# contra1575.net
KiCad netlist of a schematic drawn in EAGLE
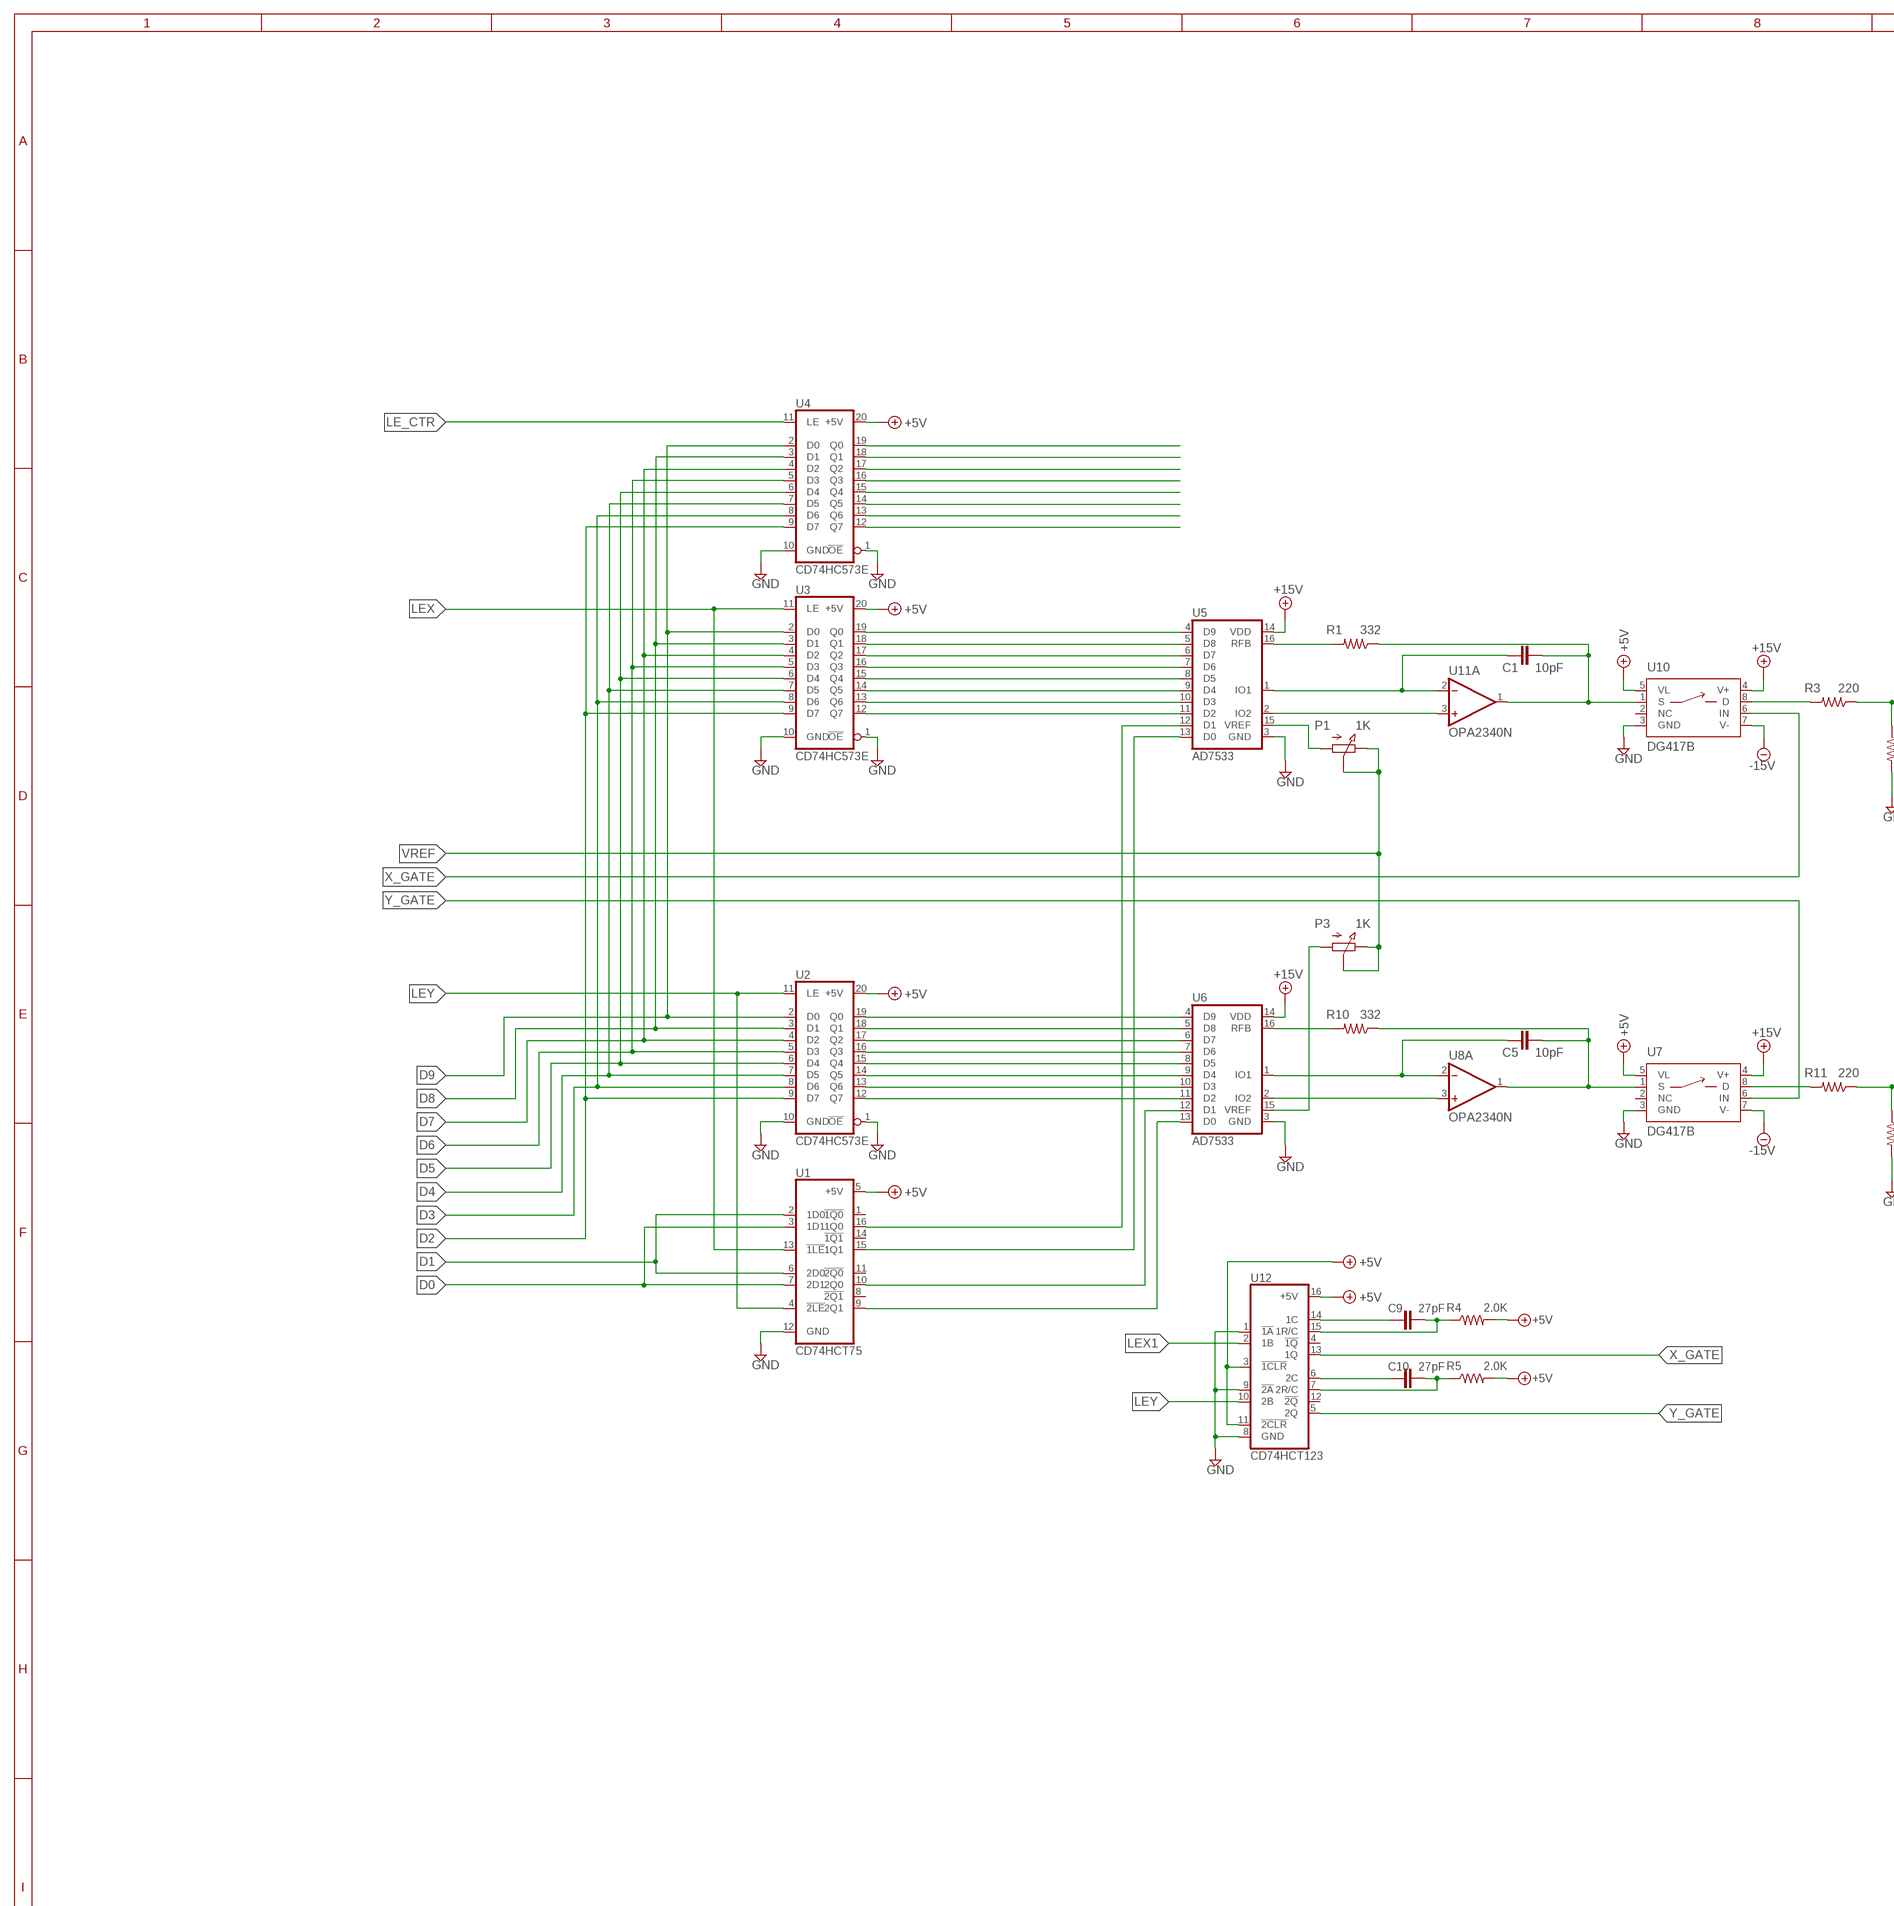
[diagram p0: schematic, sheet 1, part 1 of 2]
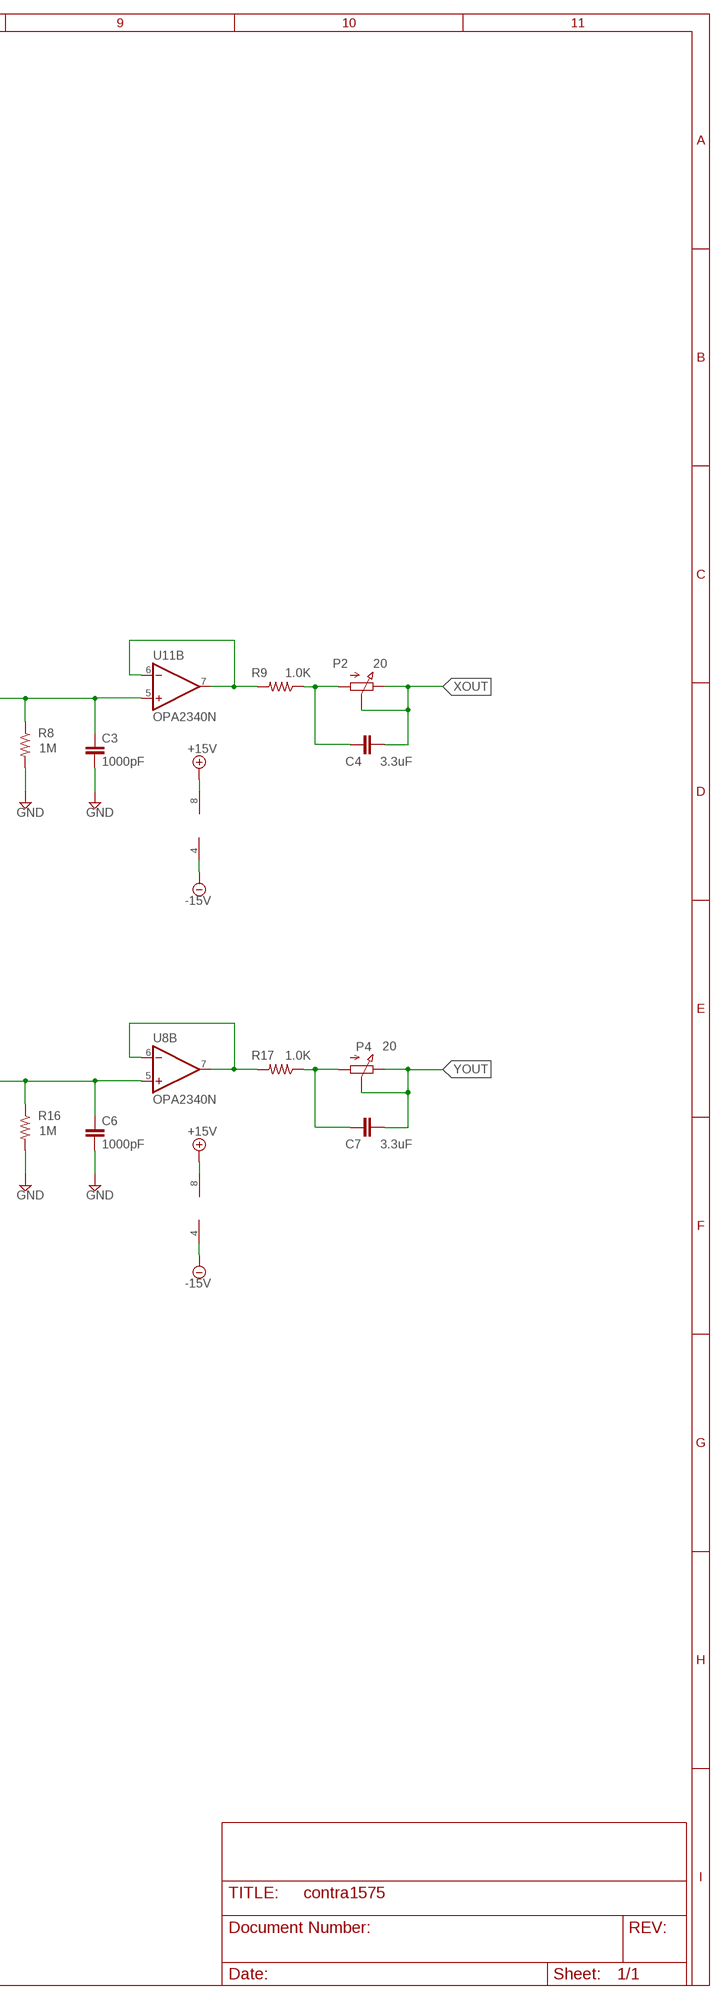
[diagram p1: schematic, sheet 1, part 2 of 2]

(export (version "E")
  (design (tool "Eeschema 10.0.6"))
  (components
    (comp (ref "C1")
      (value "10pF")
      (footprint "eagle-import:C2.5")
      (libsource (lib "eagle-import") (part "C-0.1"))
    )
    (comp (ref "C3")
      (value "1000pF")
      (footprint "eagle-import:C2.5")
      (libsource (lib "eagle-import") (part "C-0.1"))
    )
    (comp (ref "C4")
      (value "3.3uF")
      (footprint "eagle-import:MKS2B043301H00")
      (libsource (lib "eagle-import") (part "MKS2B043301H00"))
    )
    (comp (ref "C5")
      (value "10pF")
      (footprint "eagle-import:C2.5")
      (libsource (lib "eagle-import") (part "C-0.1"))
    )
    (comp (ref "C6")
      (value "1000pF")
      (footprint "eagle-import:C2.5")
      (libsource (lib "eagle-import") (part "C-0.1"))
    )
    (comp (ref "C7")
      (value "3.3uF")
      (footprint "eagle-import:MKS2B043301H00")
      (libsource (lib "eagle-import") (part "MKS2B043301H00"))
    )
    (comp (ref "C9")
      (value "27pF")
      (footprint "eagle-import:C2.5")
      (libsource (lib "eagle-import") (part "C-0.1"))
    )
    (comp (ref "C10")
      (value "27pF")
      (footprint "eagle-import:C2.5")
      (libsource (lib "eagle-import") (part "C-0.1"))
    )
    (comp (ref "P1")
      (value "1K")
      (footprint "eagle-import:3006P")
      (libsource (lib "eagle-import") (part "POT-3006P"))
    )
    (comp (ref "P2")
      (value "20")
      (footprint "eagle-import:3006P")
      (libsource (lib "eagle-import") (part "POT-3006P"))
    )
    (comp (ref "P3")
      (value "1K")
      (footprint "eagle-import:3006P")
      (libsource (lib "eagle-import") (part "POT-3006P"))
    )
    (comp (ref "P4")
      (value "20")
      (footprint "eagle-import:3006P")
      (libsource (lib "eagle-import") (part "POT-3006P"))
    )
    (comp (ref "R1")
      (value "332")
      (footprint "eagle-import:0207_10")
      (libsource (lib "eagle-import") (part "R-1/4WATT"))
    )
    (comp (ref "R3")
      (value "220")
      (footprint "eagle-import:0207_10")
      (libsource (lib "eagle-import") (part "R-1/4WATT"))
    )
    (comp (ref "R4")
      (value "2.0K")
      (footprint "eagle-import:0207_10")
      (libsource (lib "eagle-import") (part "R-1/4WATT"))
    )
    (comp (ref "R5")
      (value "2.0K")
      (footprint "eagle-import:0207_10")
      (libsource (lib "eagle-import") (part "R-1/4WATT"))
    )
    (comp (ref "R8")
      (value "1M")
      (footprint "eagle-import:0207_10")
      (libsource (lib "eagle-import") (part "R-1/4WATT"))
    )
    (comp (ref "R9")
      (value "1.0K")
      (footprint "eagle-import:0207_10")
      (libsource (lib "eagle-import") (part "R-1/4WATT"))
    )
    (comp (ref "R10")
      (value "332")
      (footprint "eagle-import:0207_10")
      (libsource (lib "eagle-import") (part "R-1/4WATT"))
    )
    (comp (ref "R11")
      (value "220")
      (footprint "eagle-import:0207_10")
      (libsource (lib "eagle-import") (part "R-1/4WATT"))
    )
    (comp (ref "R16")
      (value "1M")
      (footprint "eagle-import:0207_10")
      (libsource (lib "eagle-import") (part "R-1/4WATT"))
    )
    (comp (ref "R17")
      (value "1.0K")
      (footprint "eagle-import:0207_10")
      (libsource (lib "eagle-import") (part "R-1/4WATT"))
    )
    (comp (ref "U1")
      (value "CD74HCT75")
      (footprint "eagle-import:DIP-16")
      (libsource (lib "eagle-import") (part "CD74HCT75"))
    )
    (comp (ref "U2")
      (value "CD74HC573E")
      (footprint "eagle-import:DIP-20")
      (libsource (lib "eagle-import") (part "CD74HC573E"))
    )
    (comp (ref "U3")
      (value "CD74HC573E")
      (footprint "eagle-import:DIP-20")
      (libsource (lib "eagle-import") (part "CD74HC573E"))
    )
    (comp (ref "U4")
      (value "CD74HC573E")
      (footprint "eagle-import:DIP-20")
      (libsource (lib "eagle-import") (part "CD74HC573E"))
    )
    (comp (ref "U5")
      (value "AD7533")
      (footprint "eagle-import:DIP-16")
      (libsource (lib "eagle-import") (part "AD7533"))
    )
    (comp (ref "U6")
      (value "AD7533")
      (footprint "eagle-import:DIP-16")
      (libsource (lib "eagle-import") (part "AD7533"))
    )
    (comp (ref "U7")
      (value "DG417B")
      (footprint "eagle-import:DIP-08")
      (libsource (lib "eagle-import") (part "DG417B"))
    )
    (comp (ref "U8")
      (value "OPA2340N")
      (footprint "eagle-import:DIP-08")
      (fields (field (name "PN") "OPA2340PA"))
      (libsource (lib "eagle-import") (part "OPA2340N"))
    )
    (comp (ref "U10")
      (value "DG417B")
      (footprint "eagle-import:DIP-08")
      (libsource (lib "eagle-import") (part "DG417B"))
    )
    (comp (ref "U11")
      (value "OPA2340N")
      (footprint "eagle-import:DIP-08")
      (fields (field (name "PN") "OPA2340PA"))
      (libsource (lib "eagle-import") (part "OPA2340N"))
    )
    (comp (ref "U12")
      (value "CD74HCT123")
      (footprint "eagle-import:DIP-16")
      (libsource (lib "eagle-import") (part "CD74HCT123"))
    )
  )
  (nets
    (net (code "1") (name "+5V") (class "Default")
      (node (ref "R4") (pin "2") (pinfunction "P$2_2") (pintype "passive"))
      (node (ref "R5") (pin "2") (pinfunction "P$2_2") (pintype "passive"))
      (node (ref "U1") (pin "5") (pinfunction "+5V_5") (pintype "power_in"))
      (node (ref "U10") (pin "5") (pinfunction "VL_5") (pintype "power_in"))
      (node (ref "U12") (pin "11") (pinfunction "~{2CLR}_11") (pintype "input"))
      (node (ref "U12") (pin "16") (pinfunction "+5V_16") (pintype "power_in"))
      (node (ref "U12") (pin "3") (pinfunction "~{1CLR}_3") (pintype "input"))
      (node (ref "U2") (pin "20") (pinfunction "+5V_20") (pintype "power_in"))
      (node (ref "U3") (pin "20") (pinfunction "+5V_20") (pintype "power_in"))
      (node (ref "U4") (pin "20") (pinfunction "+5V_20") (pintype "power_in"))
      (node (ref "U7") (pin "5") (pinfunction "VL_5") (pintype "power_in"))
    )
    (net (code "2") (name "+15V") (class "Default")
      (node (ref "U10") (pin "4") (pinfunction "V+_4") (pintype "power_in"))
      (node (ref "U11") (pin "8") (pinfunction "V+_8") (pintype "power_in"))
      (node (ref "U5") (pin "14") (pinfunction "VDD_14") (pintype "power_in"))
      (node (ref "U6") (pin "14") (pinfunction "VDD_14") (pintype "power_in"))
      (node (ref "U7") (pin "4") (pinfunction "V+_4") (pintype "power_in"))
      (node (ref "U8") (pin "8") (pinfunction "V+_8") (pintype "power_in"))
    )
    (net (code "3") (name "-15V") (class "Default")
      (node (ref "U10") (pin "7") (pinfunction "V-_7") (pintype "power_in"))
      (node (ref "U11") (pin "4") (pinfunction "V-_4") (pintype "power_in"))
      (node (ref "U7") (pin "7") (pinfunction "V-_7") (pintype "power_in"))
      (node (ref "U8") (pin "4") (pinfunction "V-_4") (pintype "power_in"))
    )
    (net (code "4") (name "D0") (class "Default")
      (node (ref "U1") (pin "3") (pinfunction "1D1_3") (pintype "input"))
      (node (ref "U1") (pin "7") (pinfunction "2D1_7") (pintype "input"))
    )
    (net (code "5") (name "D1") (class "Default")
      (node (ref "U1") (pin "2") (pinfunction "1D0_2") (pintype "input"))
      (node (ref "U1") (pin "6") (pinfunction "2D0_6") (pintype "input"))
    )
    (net (code "6") (name "D2") (class "Default")
      (node (ref "U2") (pin "9") (pinfunction "D7_9") (pintype "input"))
      (node (ref "U3") (pin "9") (pinfunction "D7_9") (pintype "input"))
      (node (ref "U4") (pin "9") (pinfunction "D7_9") (pintype "input"))
    )
    (net (code "7") (name "D3") (class "Default")
      (node (ref "U2") (pin "8") (pinfunction "D6_8") (pintype "input"))
      (node (ref "U3") (pin "8") (pinfunction "D6_8") (pintype "input"))
      (node (ref "U4") (pin "8") (pinfunction "D6_8") (pintype "input"))
    )
    (net (code "8") (name "D4") (class "Default")
      (node (ref "U2") (pin "7") (pinfunction "D5_7") (pintype "input"))
      (node (ref "U3") (pin "7") (pinfunction "D5_7") (pintype "input"))
      (node (ref "U4") (pin "7") (pinfunction "D5_7") (pintype "input"))
    )
    (net (code "9") (name "D5") (class "Default")
      (node (ref "U2") (pin "6") (pinfunction "D4_6") (pintype "input"))
      (node (ref "U3") (pin "6") (pinfunction "D4_6") (pintype "input"))
      (node (ref "U4") (pin "6") (pinfunction "D4_6") (pintype "input"))
    )
    (net (code "10") (name "D6") (class "Default")
      (node (ref "U2") (pin "5") (pinfunction "D3_5") (pintype "input"))
      (node (ref "U3") (pin "5") (pinfunction "D3_5") (pintype "input"))
      (node (ref "U4") (pin "5") (pinfunction "D3_5") (pintype "input"))
    )
    (net (code "11") (name "D7") (class "Default")
      (node (ref "U2") (pin "4") (pinfunction "D2_4") (pintype "input"))
      (node (ref "U3") (pin "4") (pinfunction "D2_4") (pintype "input"))
      (node (ref "U4") (pin "4") (pinfunction "D2_4") (pintype "input"))
    )
    (net (code "12") (name "D8") (class "Default")
      (node (ref "U2") (pin "3") (pinfunction "D1_3") (pintype "input"))
      (node (ref "U3") (pin "3") (pinfunction "D1_3") (pintype "input"))
      (node (ref "U4") (pin "3") (pinfunction "D1_3") (pintype "input"))
    )
    (net (code "13") (name "D9") (class "Default")
      (node (ref "U2") (pin "2") (pinfunction "D0_2") (pintype "input"))
      (node (ref "U3") (pin "2") (pinfunction "D0_2") (pintype "input"))
      (node (ref "U4") (pin "2") (pinfunction "D0_2") (pintype "input"))
    )
    (net (code "14") (name "GND") (class "Default")
      (node (ref "C3") (pin "2") (pinfunction "2_2") (pintype "passive"))
      (node (ref "C6") (pin "2") (pinfunction "2_2") (pintype "passive"))
      (node (ref "R16") (pin "2") (pinfunction "P$2_2") (pintype "passive"))
      (node (ref "R8") (pin "2") (pinfunction "P$2_2") (pintype "passive"))
      (node (ref "U1") (pin "12") (pinfunction "GND_12") (pintype "power_in"))
      (node (ref "U10") (pin "3") (pinfunction "GND_3") (pintype "power_in"))
      (node (ref "U12") (pin "1") (pinfunction "~{1A}_1") (pintype "input"))
      (node (ref "U12") (pin "8") (pinfunction "GND_8") (pintype "power_in"))
      (node (ref "U12") (pin "9") (pinfunction "~{2A}_9") (pintype "input"))
      (node (ref "U2") (pin "1") (pinfunction "~{OE}_1") (pintype "input"))
      (node (ref "U2") (pin "10") (pinfunction "GND_10") (pintype "power_in"))
      (node (ref "U3") (pin "1") (pinfunction "~{OE}_1") (pintype "input"))
      (node (ref "U3") (pin "10") (pinfunction "GND_10") (pintype "power_in"))
      (node (ref "U4") (pin "1") (pinfunction "~{OE}_1") (pintype "input"))
      (node (ref "U4") (pin "10") (pinfunction "GND_10") (pintype "power_in"))
      (node (ref "U5") (pin "3") (pinfunction "GND_3") (pintype "power_in"))
      (node (ref "U6") (pin "3") (pinfunction "GND_3") (pintype "power_in"))
      (node (ref "U7") (pin "3") (pinfunction "GND_3") (pintype "power_in"))
    )
    (net (code "15") (name "LEX") (class "Default")
      (node (ref "U1") (pin "13") (pinfunction "~{1LE}_13") (pintype "input"))
      (node (ref "U3") (pin "11") (pinfunction "LE_11") (pintype "input"))
    )
    (net (code "16") (name "LEX1") (class "Default")
      (node (ref "U12") (pin "2") (pinfunction "1B_2") (pintype "input"))
    )
    (net (code "17") (name "LEY") (class "Default")
      (node (ref "U1") (pin "4") (pinfunction "~{2LE}_4") (pintype "input"))
      (node (ref "U2") (pin "11") (pinfunction "LE_11") (pintype "input"))
    )
    (net (code "18") (name "LE_CTR") (class "Default")
      (node (ref "U4") (pin "11") (pinfunction "LE_11") (pintype "input"))
    )
    (net (code "19") (name "Net-(P1-A)") (class "Default")
      (node (ref "P1") (pin "1") (pinfunction "A_1") (pintype "passive"))
      (node (ref "U5") (pin "15") (pinfunction "VREF_15") (pintype "power_in"))
    )
    (net (code "20") (name "Net-(P2-A)") (class "Default")
      (node (ref "C4") (pin "1") (pinfunction "1_1") (pintype "passive"))
      (node (ref "P2") (pin "1") (pinfunction "A_1") (pintype "passive"))
      (node (ref "R9") (pin "1") (pinfunction "P$1_1") (pintype "passive"))
    )
    (net (code "21") (name "Net-(P3-A)") (class "Default")
      (node (ref "P3") (pin "1") (pinfunction "A_1") (pintype "passive"))
      (node (ref "U6") (pin "15") (pinfunction "VREF_15") (pintype "power_in"))
    )
    (net (code "22") (name "Net-(P4-A)") (class "Default")
      (node (ref "C7") (pin "1") (pinfunction "1_1") (pintype "passive"))
      (node (ref "P4") (pin "1") (pinfunction "A_1") (pintype "passive"))
      (node (ref "R17") (pin "1") (pinfunction "P$1_1") (pintype "passive"))
    )
    (net (code "23") (name "Net-(R1-P$1)") (class "Default")
      (node (ref "C1") (pin "2") (pinfunction "2_2") (pintype "passive"))
      (node (ref "R1") (pin "1") (pinfunction "P$1_1") (pintype "passive"))
      (node (ref "U10") (pin "1") (pinfunction "S_1") (pintype "passive"))
      (node (ref "U11") (pin "1") (pinfunction "OUT_1") (pintype "output"))
    )
    (net (code "24") (name "Net-(R1-P$2)") (class "Default")
      (node (ref "R1") (pin "2") (pinfunction "P$2_2") (pintype "passive"))
      (node (ref "U5") (pin "16") (pinfunction "RFB_16") (pintype "input"))
    )
    (net (code "25") (name "Net-(R3-P$1)") (class "Default")
      (node (ref "C3") (pin "1") (pinfunction "1_1") (pintype "passive"))
      (node (ref "R3") (pin "1") (pinfunction "P$1_1") (pintype "passive"))
      (node (ref "R8") (pin "1") (pinfunction "P$1_1") (pintype "passive"))
      (node (ref "U11") (pin "5") (pinfunction "+IN_5") (pintype "input"))
    )
    (net (code "26") (name "Net-(R3-P$2)") (class "Default")
      (node (ref "R3") (pin "2") (pinfunction "P$2_2") (pintype "passive"))
      (node (ref "U10") (pin "8") (pinfunction "D_8") (pintype "passive"))
    )
    (net (code "27") (name "Net-(R4-P$1)") (class "Default")
      (node (ref "C9") (pin "2") (pinfunction "2_2") (pintype "passive"))
      (node (ref "R4") (pin "1") (pinfunction "P$1_1") (pintype "passive"))
      (node (ref "U12") (pin "15") (pinfunction "1R/C_15") (pintype "passive"))
    )
    (net (code "28") (name "Net-(R5-P$1)") (class "Default")
      (node (ref "C10") (pin "2") (pinfunction "2_2") (pintype "passive"))
      (node (ref "R5") (pin "1") (pinfunction "P$1_1") (pintype "passive"))
      (node (ref "U12") (pin "7") (pinfunction "2R/C_7") (pintype "passive"))
    )
    (net (code "29") (name "Net-(R9-P$2)") (class "Default")
      (node (ref "R9") (pin "2") (pinfunction "P$2_2") (pintype "passive"))
      (node (ref "U11") (pin "6") (pinfunction "-IN_6") (pintype "input"))
      (node (ref "U11") (pin "7") (pinfunction "OUT_7") (pintype "output"))
    )
    (net (code "30") (name "Net-(R10-P$1)") (class "Default")
      (node (ref "C5") (pin "2") (pinfunction "2_2") (pintype "passive"))
      (node (ref "R10") (pin "1") (pinfunction "P$1_1") (pintype "passive"))
      (node (ref "U7") (pin "1") (pinfunction "S_1") (pintype "passive"))
      (node (ref "U8") (pin "1") (pinfunction "OUT_1") (pintype "output"))
    )
    (net (code "31") (name "Net-(R10-P$2)") (class "Default")
      (node (ref "R10") (pin "2") (pinfunction "P$2_2") (pintype "passive"))
      (node (ref "U6") (pin "16") (pinfunction "RFB_16") (pintype "input"))
    )
    (net (code "32") (name "Net-(R11-P$1)") (class "Default")
      (node (ref "C6") (pin "1") (pinfunction "1_1") (pintype "passive"))
      (node (ref "R11") (pin "1") (pinfunction "P$1_1") (pintype "passive"))
      (node (ref "R16") (pin "1") (pinfunction "P$1_1") (pintype "passive"))
      (node (ref "U8") (pin "5") (pinfunction "+IN_5") (pintype "input"))
    )
    (net (code "33") (name "Net-(R11-P$2)") (class "Default")
      (node (ref "R11") (pin "2") (pinfunction "P$2_2") (pintype "passive"))
      (node (ref "U7") (pin "8") (pinfunction "D_8") (pintype "passive"))
    )
    (net (code "34") (name "Net-(R17-P$2)") (class "Default")
      (node (ref "R17") (pin "2") (pinfunction "P$2_2") (pintype "passive"))
      (node (ref "U8") (pin "6") (pinfunction "-IN_6") (pintype "input"))
      (node (ref "U8") (pin "7") (pinfunction "OUT_7") (pintype "output"))
    )
    (net (code "35") (name "Net-(U1-1Q0)") (class "Default")
      (node (ref "U1") (pin "16") (pinfunction "1Q0_16") (pintype "output"))
      (node (ref "U5") (pin "12") (pinfunction "D1_12") (pintype "input"))
    )
    (net (code "36") (name "Net-(U1-1Q1)") (class "Default")
      (node (ref "U1") (pin "15") (pinfunction "1Q1_15") (pintype "output"))
      (node (ref "U5") (pin "13") (pinfunction "D0_13") (pintype "input"))
    )
    (net (code "37") (name "Net-(U1-2Q0)") (class "Default")
      (node (ref "U1") (pin "10") (pinfunction "2Q0_10") (pintype "output"))
      (node (ref "U6") (pin "12") (pinfunction "D1_12") (pintype "input"))
    )
    (net (code "38") (name "Net-(U1-2Q1)") (class "Default")
      (node (ref "U1") (pin "9") (pinfunction "2Q1_9") (pintype "output"))
      (node (ref "U6") (pin "13") (pinfunction "D0_13") (pintype "input"))
    )
    (net (code "39") (name "Net-(U2-Q0)") (class "Default")
      (node (ref "U2") (pin "19") (pinfunction "Q0_19") (pintype "tri_state"))
      (node (ref "U6") (pin "4") (pinfunction "D9_4") (pintype "input"))
    )
    (net (code "40") (name "Net-(U2-Q1)") (class "Default")
      (node (ref "U2") (pin "18") (pinfunction "Q1_18") (pintype "tri_state"))
      (node (ref "U6") (pin "5") (pinfunction "D8_5") (pintype "input"))
    )
    (net (code "41") (name "Net-(U2-Q2)") (class "Default")
      (node (ref "U2") (pin "17") (pinfunction "Q2_17") (pintype "tri_state"))
      (node (ref "U6") (pin "6") (pinfunction "D7_6") (pintype "input"))
    )
    (net (code "42") (name "Net-(U2-Q3)") (class "Default")
      (node (ref "U2") (pin "16") (pinfunction "Q3_16") (pintype "tri_state"))
      (node (ref "U6") (pin "7") (pinfunction "D6_7") (pintype "input"))
    )
    (net (code "43") (name "Net-(U2-Q4)") (class "Default")
      (node (ref "U2") (pin "15") (pinfunction "Q4_15") (pintype "tri_state"))
      (node (ref "U6") (pin "8") (pinfunction "D5_8") (pintype "input"))
    )
    (net (code "44") (name "Net-(U2-Q5)") (class "Default")
      (node (ref "U2") (pin "14") (pinfunction "Q5_14") (pintype "tri_state"))
      (node (ref "U6") (pin "9") (pinfunction "D4_9") (pintype "input"))
    )
    (net (code "45") (name "Net-(U2-Q6)") (class "Default")
      (node (ref "U2") (pin "13") (pinfunction "Q6_13") (pintype "tri_state"))
      (node (ref "U6") (pin "10") (pinfunction "D3_10") (pintype "input"))
    )
    (net (code "46") (name "Net-(U2-Q7)") (class "Default")
      (node (ref "U2") (pin "12") (pinfunction "Q7_12") (pintype "tri_state"))
      (node (ref "U6") (pin "11") (pinfunction "D2_11") (pintype "input"))
    )
    (net (code "47") (name "Net-(U3-Q0)") (class "Default")
      (node (ref "U3") (pin "19") (pinfunction "Q0_19") (pintype "tri_state"))
      (node (ref "U5") (pin "4") (pinfunction "D9_4") (pintype "input"))
    )
    (net (code "48") (name "Net-(U3-Q1)") (class "Default")
      (node (ref "U3") (pin "18") (pinfunction "Q1_18") (pintype "tri_state"))
      (node (ref "U5") (pin "5") (pinfunction "D8_5") (pintype "input"))
    )
    (net (code "49") (name "Net-(U3-Q2)") (class "Default")
      (node (ref "U3") (pin "17") (pinfunction "Q2_17") (pintype "tri_state"))
      (node (ref "U5") (pin "6") (pinfunction "D7_6") (pintype "input"))
    )
    (net (code "50") (name "Net-(U3-Q3)") (class "Default")
      (node (ref "U3") (pin "16") (pinfunction "Q3_16") (pintype "tri_state"))
      (node (ref "U5") (pin "7") (pinfunction "D6_7") (pintype "input"))
    )
    (net (code "51") (name "Net-(U3-Q4)") (class "Default")
      (node (ref "U3") (pin "15") (pinfunction "Q4_15") (pintype "tri_state"))
      (node (ref "U5") (pin "8") (pinfunction "D5_8") (pintype "input"))
    )
    (net (code "52") (name "Net-(U3-Q5)") (class "Default")
      (node (ref "U3") (pin "14") (pinfunction "Q5_14") (pintype "tri_state"))
      (node (ref "U5") (pin "9") (pinfunction "D4_9") (pintype "input"))
    )
    (net (code "53") (name "Net-(U3-Q6)") (class "Default")
      (node (ref "U3") (pin "13") (pinfunction "Q6_13") (pintype "tri_state"))
      (node (ref "U5") (pin "10") (pinfunction "D3_10") (pintype "input"))
    )
    (net (code "54") (name "Net-(U3-Q7)") (class "Default")
      (node (ref "U3") (pin "12") (pinfunction "Q7_12") (pintype "tri_state"))
      (node (ref "U5") (pin "11") (pinfunction "D2_11") (pintype "input"))
    )
    (net (code "55") (name "Net-(U6-IO1)") (class "Default")
      (node (ref "C5") (pin "1") (pinfunction "1_1") (pintype "passive"))
      (node (ref "U6") (pin "1") (pinfunction "IO1_1") (pintype "output"))
      (node (ref "U8") (pin "2") (pinfunction "-IN_2") (pintype "input"))
    )
    (net (code "56") (name "Net-(U6-IO2)") (class "Default")
      (node (ref "U6") (pin "2") (pinfunction "IO2_2") (pintype "output"))
      (node (ref "U8") (pin "3") (pinfunction "+IN_3") (pintype "input"))
    )
    (net (code "57") (name "Net-(U11A-+IN)") (class "Default")
      (node (ref "U11") (pin "3") (pinfunction "+IN_3") (pintype "input"))
      (node (ref "U5") (pin "2") (pinfunction "IO2_2") (pintype "output"))
    )
    (net (code "58") (name "Net-(U11A--IN)") (class "Default")
      (node (ref "C1") (pin "1") (pinfunction "1_1") (pintype "passive"))
      (node (ref "U11") (pin "2") (pinfunction "-IN_2") (pintype "input"))
      (node (ref "U5") (pin "1") (pinfunction "IO1_1") (pintype "output"))
    )
    (net (code "59") (name "Net-(U12-1C)") (class "Default")
      (node (ref "C9") (pin "1") (pinfunction "1_1") (pintype "passive"))
      (node (ref "U12") (pin "14") (pinfunction "1C_14") (pintype "passive"))
    )
    (net (code "60") (name "Net-(U12-2C)") (class "Default")
      (node (ref "C10") (pin "1") (pinfunction "1_1") (pintype "passive"))
      (node (ref "U12") (pin "6") (pinfunction "2C_6") (pintype "passive"))
    )
    (net (code "61") (name "VREF") (class "Default")
      (node (ref "P1") (pin "2") (pinfunction "S_2") (pintype "passive"))
      (node (ref "P1") (pin "3") (pinfunction "E_3") (pintype "passive"))
      (node (ref "P3") (pin "2") (pinfunction "S_2") (pintype "passive"))
      (node (ref "P3") (pin "3") (pinfunction "E_3") (pintype "passive"))
    )
    (net (code "62") (name "XOUT") (class "Default")
      (node (ref "C4") (pin "2") (pinfunction "2_2") (pintype "passive"))
      (node (ref "P2") (pin "2") (pinfunction "S_2") (pintype "passive"))
      (node (ref "P2") (pin "3") (pinfunction "E_3") (pintype "passive"))
    )
    (net (code "63") (name "X_GATE") (class "Default")
      (node (ref "U10") (pin "6") (pinfunction "IN_6") (pintype "input"))
      (node (ref "U12") (pin "13") (pinfunction "1Q_13") (pintype "output"))
    )
    (net (code "64") (name "YOUT") (class "Default")
      (node (ref "C7") (pin "2") (pinfunction "2_2") (pintype "passive"))
      (node (ref "P4") (pin "2") (pinfunction "S_2") (pintype "passive"))
      (node (ref "P4") (pin "3") (pinfunction "E_3") (pintype "passive"))
    )
    (net (code "65") (name "Y_GATE") (class "Default")
      (node (ref "U12") (pin "5") (pinfunction "2Q_5") (pintype "output"))
      (node (ref "U7") (pin "6") (pinfunction "IN_6") (pintype "input"))
    )
    (net (code "66") (name "unconnected-(U1-~{1Q0}-Pad1)") (class "Default")
      (node (ref "U1") (pin "1") (pinfunction "~{1Q0}_1") (pintype "output"))
    )
    (net (code "67") (name "unconnected-(U1-~{1Q1}-Pad14)") (class "Default")
      (node (ref "U1") (pin "14") (pinfunction "~{1Q1}_14") (pintype "output"))
    )
    (net (code "68") (name "unconnected-(U1-~{2Q0}-Pad11)") (class "Default")
      (node (ref "U1") (pin "11") (pinfunction "~{2Q0}_11") (pintype "output"))
    )
    (net (code "69") (name "unconnected-(U1-~{2Q1}-Pad8)") (class "Default")
      (node (ref "U1") (pin "8") (pinfunction "~{2Q1}_8") (pintype "output"))
    )
    (net (code "70") (name "unconnected-(U4-Q0-Pad19)") (class "Default")
      (node (ref "U4") (pin "19") (pinfunction "Q0_19") (pintype "tri_state"))
    )
    (net (code "71") (name "unconnected-(U4-Q1-Pad18)") (class "Default")
      (node (ref "U4") (pin "18") (pinfunction "Q1_18") (pintype "tri_state"))
    )
    (net (code "72") (name "unconnected-(U4-Q2-Pad17)") (class "Default")
      (node (ref "U4") (pin "17") (pinfunction "Q2_17") (pintype "tri_state"))
    )
    (net (code "73") (name "unconnected-(U4-Q3-Pad16)") (class "Default")
      (node (ref "U4") (pin "16") (pinfunction "Q3_16") (pintype "tri_state"))
    )
    (net (code "74") (name "unconnected-(U4-Q4-Pad15)") (class "Default")
      (node (ref "U4") (pin "15") (pinfunction "Q4_15") (pintype "tri_state"))
    )
    (net (code "75") (name "unconnected-(U4-Q5-Pad14)") (class "Default")
      (node (ref "U4") (pin "14") (pinfunction "Q5_14") (pintype "tri_state"))
    )
    (net (code "76") (name "unconnected-(U4-Q6-Pad13)") (class "Default")
      (node (ref "U4") (pin "13") (pinfunction "Q6_13") (pintype "tri_state"))
    )
    (net (code "77") (name "unconnected-(U4-Q7-Pad12)") (class "Default")
      (node (ref "U4") (pin "12") (pinfunction "Q7_12") (pintype "tri_state"))
    )
    (net (code "78") (name "unconnected-(U7-NC-Pad2)") (class "Default")
      (node (ref "U7") (pin "2") (pinfunction "NC_2") (pintype "no_connect"))
    )
    (net (code "79") (name "unconnected-(U10-NC-Pad2)") (class "Default")
      (node (ref "U10") (pin "2") (pinfunction "NC_2") (pintype "no_connect"))
    )
    (net (code "80") (name "unconnected-(U12-2B-Pad10)") (class "Default")
      (node (ref "U12") (pin "10") (pinfunction "2B_10") (pintype "input"))
    )
    (net (code "81") (name "unconnected-(U12-~{1Q}-Pad4)") (class "Default")
      (node (ref "U12") (pin "4") (pinfunction "~{1Q}_4") (pintype "output"))
    )
    (net (code "82") (name "unconnected-(U12-~{2Q}-Pad12)") (class "Default")
      (node (ref "U12") (pin "12") (pinfunction "~{2Q}_12") (pintype "output"))
    )
  )
)
